# PSM_components.net
KiCad netlist of a schematic drawn in Altium Designer
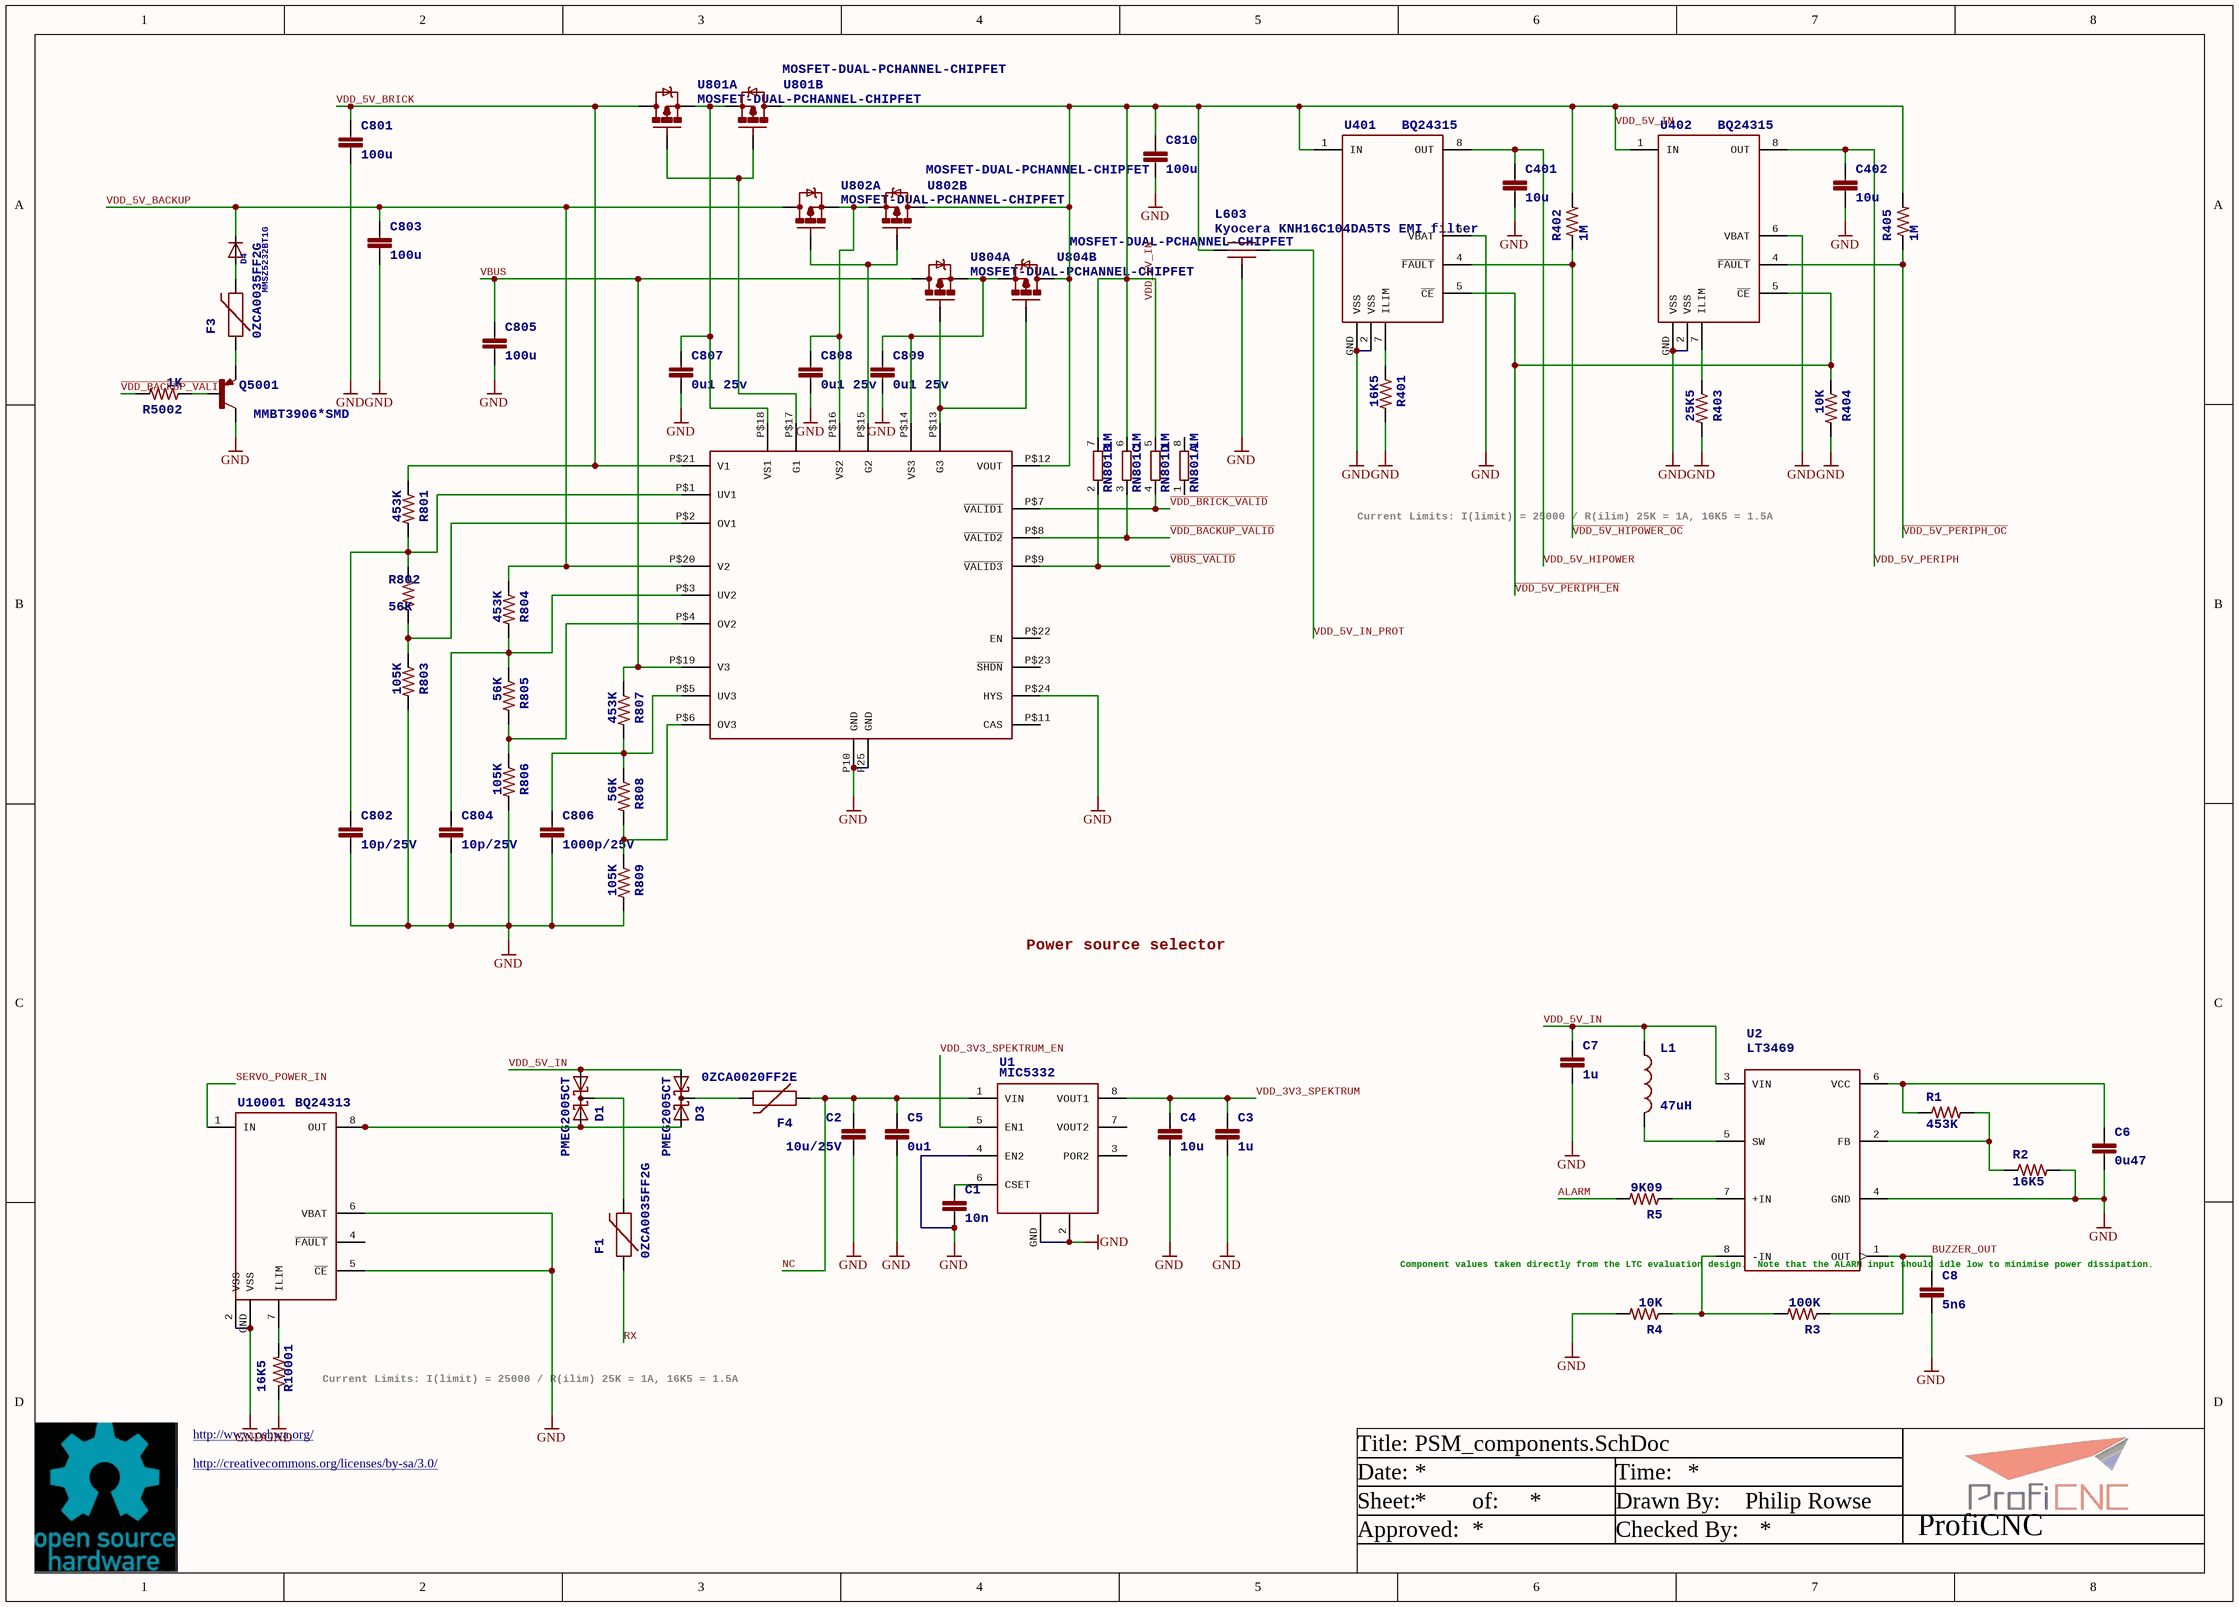
[diagram p0: PSM_components.SchDoc]

(export (version "E")
  (design (tool "Eeschema 10.0.6"))
  (components
    (comp (ref "C1") (value "10n") (footprint "PSM:0402-CAP") (libsource (lib "PSM_REV_C") (part "CAP0402")))
    (comp (ref "C2")
      (value "10u/25V")
      (footprint "PSM:0805-CAP")
      (libsource (lib "PSM_REV_C") (part "CAP0805"))
    )
    (comp (ref "C3") (value "1u") (footprint "PSM:0603-CAP") (libsource (lib "PSM_REV_C") (part "CAP0603")))
    (comp (ref "C4") (value "10u") (footprint "PSM:0603-CAP") (libsource (lib "PSM_REV_C") (part "CAP0603")))
    (comp (ref "C5") (value "0u1") (footprint "PSM:0402-CAP") (libsource (lib "PSM_REV_C") (part "CAP0402")))
    (comp (ref "C6") (value "0u47") (footprint "PSM:0402-CAP") (libsource (lib "PSM_REV_C") (part "CAP0402")))
    (comp (ref "C7") (value "1u") (footprint "PSM:0603-CAP") (libsource (lib "PSM_REV_C") (part "CAP0603")))
    (comp (ref "C8") (value "5n6") (footprint "PSM:0402-CAP") (libsource (lib "PSM_REV_C") (part "CAP0402")))
    (comp (ref "C401")
      (value "10u")
      (footprint "PSM:0603-CAP")
      (libsource (lib "PSM_REV_C") (part "CAP0603"))
    )
    (comp (ref "C402")
      (value "10u")
      (footprint "PSM:0603-CAP")
      (libsource (lib "PSM_REV_C") (part "CAP0603"))
    )
    (comp (ref "C801")
      (value "100u")
      (footprint "PSM:1206-CAP")
      (libsource (lib "PSM_REV_C") (part "CAP1206"))
    )
    (comp (ref "C802")
      (value "10p/25V")
      (footprint "PSM:0402-CAP")
      (libsource (lib "PSM_REV_C") (part "CAP0402"))
    )
    (comp (ref "C803")
      (value "100u")
      (footprint "PSM:1206-CAP")
      (libsource (lib "PSM_REV_C") (part "CAP1206"))
    )
    (comp (ref "C804")
      (value "10p/25V")
      (footprint "PSM:0402-CAP")
      (libsource (lib "PSM_REV_C") (part "CAP0402"))
    )
    (comp (ref "C805")
      (value "100u")
      (footprint "PSM:1206-CAP")
      (libsource (lib "PSM_REV_C") (part "CAP1206"))
    )
    (comp (ref "C806")
      (value "1000p/25V")
      (footprint "PSM:0402-CAP")
      (libsource (lib "PSM_REV_C") (part "CAP0402"))
    )
    (comp (ref "C807")
      (value "0u1 25v")
      (footprint "PSM:0402-CAP")
      (libsource (lib "PSM_REV_C") (part "CAP0402"))
    )
    (comp (ref "C808")
      (value "0u1 25v")
      (footprint "PSM:0402-CAP")
      (libsource (lib "PSM_REV_C") (part "CAP0402"))
    )
    (comp (ref "C809")
      (value "0u1 25v")
      (footprint "PSM:0402-CAP")
      (libsource (lib "PSM_REV_C") (part "CAP0402"))
    )
    (comp (ref "C810")
      (value "100u")
      (footprint "PSM:1206-CAP")
      (libsource (lib "PSM_REV_C") (part "CAP1206"))
    )
    (comp (ref "D1")
      (value "PMEG2005CT")
      (footprint "PSM:SOT23-3")
      (libsource (lib "PSM_REV_C") (part "PMEG2005CT"))
    )
    (comp (ref "D3")
      (value "PMEG2005CT")
      (footprint "PSM:SOT23-3")
      (libsource (lib "PSM_REV_C") (part "PMEG2005CT"))
    )
    (comp (ref "D4")
      (value "MMSZ5232BT1G")
      (footprint "PSM:SOD-123")
      (libsource (lib "PSM_REV_C") (part "DIODESOD-123"))
    )
    (comp (ref "F1")
      (value "0ZCA0035FF2G")
      (footprint "PSM:PTC-1206")
      (libsource (lib "PSM_REV_C") (part "PTCSMD"))
    )
    (comp (ref "F3")
      (value "0ZCA0035FF2G")
      (footprint "PSM:PTC-1206")
      (libsource (lib "PSM") (part "PTCSMD"))
    )
    (comp (ref "F4")
      (value "0ZCA0020FF2E")
      (footprint "PSM:PTC-1206")
      (libsource (lib "PSM_REV_C") (part "PTCSMD"))
    )
    (comp (ref "L1")
      (value "47uH")
      (footprint "PSM:0805-IND")
      (libsource (lib "PSM_REV_C") (part "INDUCTOR0805"))
    )
    (comp (ref "L603")
      (value "Kyocera KNH16C104DA5TS EMI filter")
      (footprint "PSM:KYOCERA-KNH16-DA")
      (libsource (lib "PSM_REV_C") (part "KNH16C104DA5TS"))
    )
    (comp (ref "Q5001")
      (value "MMBT3906*SMD")
      (footprint "PSM:SOT23-BEC")
      (libsource (lib "PSM_REV_C") (part "MMBT3906*SMD"))
    )
    (comp (ref "R1")
      (value "453K")
      (footprint "PSM:0402-RES")
      (libsource (lib "PSM_REV_C") (part "RESISTOR0402-RES"))
    )
    (comp (ref "R2")
      (value "16K5")
      (footprint "PSM:0402-RES")
      (libsource (lib "PSM_REV_C") (part "RESISTOR0402-RES"))
    )
    (comp (ref "R3")
      (value "100K")
      (footprint "PSM:0402-RES")
      (libsource (lib "PSM_REV_C") (part "RESISTOR0402-RES"))
    )
    (comp (ref "R4")
      (value "10K")
      (footprint "PSM:0402-RES")
      (libsource (lib "PSM_REV_C") (part "RESISTOR0402-RES"))
    )
    (comp (ref "R5")
      (value "9K09")
      (footprint "PSM:0402-RES")
      (libsource (lib "PSM_REV_C") (part "RESISTOR0402-RES"))
    )
    (comp (ref "R401")
      (value "16K5")
      (footprint "PSM:0402-RES")
      (libsource (lib "altium-import") (part "root_3_RESISTOR0402-RES_"))
    )
    (comp (ref "R402")
      (value "1M")
      (footprint "PSM:0402-RES")
      (libsource (lib "PSM_REV_C") (part "RESISTOR0402-RES"))
    )
    (comp (ref "R403")
      (value "25K5")
      (footprint "PSM:0402-RES")
      (libsource (lib "PSM_REV_C") (part "RESISTOR0402-RES"))
    )
    (comp (ref "R404")
      (value "10K")
      (footprint "PSM:0402-RES")
      (libsource (lib "PSM_REV_C") (part "RESISTOR0402-RES"))
    )
    (comp (ref "R405")
      (value "1M")
      (footprint "PSM:0402-RES")
      (libsource (lib "PSM_REV_C") (part "RESISTOR0402-RES"))
    )
    (comp (ref "R801")
      (value "453K")
      (footprint "PSM:0402-RES")
      (libsource (lib "PSM_REV_C") (part "RESISTOR0402-RES"))
    )
    (comp (ref "R802")
      (value "56K")
      (footprint "PSM:0402-RES")
      (libsource (lib "PSM_REV_C") (part "RESISTOR0402-RES_1"))
    )
    (comp (ref "R803")
      (value "105K")
      (footprint "PSM:0402-RES")
      (libsource (lib "PSM_REV_C") (part "RESISTOR0402-RES"))
    )
    (comp (ref "R804")
      (value "453K")
      (footprint "PSM:0402-RES")
      (libsource (lib "PSM_REV_C") (part "RESISTOR0402-RES"))
    )
    (comp (ref "R805")
      (value "56K")
      (footprint "PSM:0402-RES")
      (libsource (lib "PSM_REV_C") (part "RESISTOR0402-RES"))
    )
    (comp (ref "R806")
      (value "105K")
      (footprint "PSM:0402-RES")
      (libsource (lib "PSM_REV_C") (part "RESISTOR0402-RES"))
    )
    (comp (ref "R807")
      (value "453K")
      (footprint "PSM:0402-RES")
      (libsource (lib "PSM_REV_C") (part "RESISTOR0402-RES"))
    )
    (comp (ref "R808")
      (value "56K")
      (footprint "PSM:0402-RES")
      (libsource (lib "PSM_REV_C") (part "RESISTOR0402-RES"))
    )
    (comp (ref "R809")
      (value "105K")
      (footprint "PSM:0402-RES")
      (libsource (lib "PSM_REV_C") (part "RESISTOR0402-RES"))
    )
    (comp (ref "R5002")
      (value "1K")
      (footprint "PSM:0402-RES")
      (libsource (lib "PSM_REV_C") (part "RESISTOR0402-RES"))
    )
    (comp (ref "R10001")
      (value "16K5")
      (footprint "PSM:0402-RES")
      (libsource (lib "PSM_REV_C") (part "RESISTOR0402-RES"))
    )
    (comp (ref "RN801")
      (value "1M")
      (footprint "EXB28V")
      (description "RES ARRAY 1M OHM 4 RES 0804")
      (libsource (lib "PSM_REV_C") (part "4R-NEXB28V"))
    )
    (comp (ref "U1")
      (value "MIC5332")
      (footprint "PSM:MLF-8-EPAD")
      (libsource (lib "PSM_REV_C") (part "MIC5332"))
    )
    (comp (ref "U2") (value "LT3469") (footprint "PSM:SOT23-8") (libsource (lib "PSM_REV_C") (part "LT3469")))
    (comp (ref "U401")
      (value "BQ24315")
      (footprint "QFN8-DSG")
      (libsource (lib "PSM_REV_C") (part "BQ24315"))
    )
    (comp (ref "U402")
      (value "BQ24315")
      (footprint "QFN8-DSG")
      (libsource (lib "PSM_REV_C") (part "BQ24315"))
    )
    (comp (ref "U801")
      (value "MOSFET-DUAL-PCHANNEL-CHIPFET")
      (footprint "PSM:1206-8")
      (description "MOSFET 2P-CH 20V 2.9A CHIPFET")
      (libsource (lib "") (part "MOSFET-DUAL-PCHANNEL-CHIPFET_1"))
    )
    (comp (ref "U802")
      (value "MOSFET-DUAL-PCHANNEL-CHIPFET")
      (footprint "PSM:1206-8")
      (description "MOSFET 2P-CH 20V 2.9A CHIPFET")
      (libsource (lib "") (part "MOSFET-DUAL-PCHANNEL-CHIPFET_1"))
    )
    (comp (ref "U803")
      (value "LTC4417")
      (footprint "PSM:MO-220")
      (libsource (lib "altium-import") (part "root_0_LTC4117_"))
    )
    (comp (ref "U804")
      (value "MOSFET-DUAL-PCHANNEL-CHIPFET")
      (footprint "PSM:1206-8")
      (description "MOSFET 2P-CH 20V 2.9A CHIPFET")
      (libsource (lib "PSM_REV_C") (part "MOSFET-DUAL-PCHANNEL-CHIPFET"))
    )
    (comp (ref "U10001")
      (value "BQ24313")
      (footprint "QFN8-DSG")
      (libsource (lib "PSM_REV_C") (part "BQ24313"))
    )
  )
  (nets
    (net (code "1") (name "/ALARM") (class "Default")
      (node (ref "R5") (pin "P$2") (pinfunction "2_P$2") (pintype "passive"))
    )
    (net (code "2") (name "/BUZZER_OUT") (class "Default")
      (node (ref "C8") (pin "P$1") (pinfunction "1_P$1") (pintype "passive"))
      (node (ref "R3") (pin "P$1") (pinfunction "1_P$1") (pintype "passive"))
      (node (ref "U2") (pin "1") (pinfunction "OUT_1") (pintype "output"))
    )
    (net (code "3") (name "/NC") (class "Default")
      (node (ref "C2") (pin "P$1") (pinfunction "1_P$1") (pintype "passive"))
      (node (ref "C5") (pin "P$1") (pinfunction "1_P$1") (pintype "passive"))
      (node (ref "F4") (pin "1") (pinfunction "1_1") (pintype "passive"))
      (node (ref "U1") (pin "1") (pinfunction "VIN_1") (pintype "passive"))
    )
    (net (code "4") (name "/RX") (class "Default")
      (node (ref "F1") (pin "1") (pinfunction "1_1") (pintype "passive"))
    )
    (net (code "5") (name "/SERVO_POWER_IN") (class "Default")
      (node (ref "U10001") (pin "1") (pinfunction "IN_1") (pintype "passive"))
    )
    (net (code "6") (name "/VBUS") (class "Default")
      (node (ref "C805") (pin "P$1") (pinfunction "1_P$1") (pintype "passive"))
      (node (ref "R807") (pin "P$1") (pinfunction "1_P$1") (pintype "passive"))
      (node (ref "U803") (pin "P$19") (pinfunction "V3_P$19") (pintype "passive"))
      (node (ref "U804") (pin "P7") (pinfunction "D_P7") (pintype "passive"))
    )
    (net (code "7") (name "/VDD_3V3_SPEKTRUM") (class "Default")
      (node (ref "C3") (pin "P$1") (pinfunction "1_P$1") (pintype "passive"))
      (node (ref "C4") (pin "P$1") (pinfunction "1_P$1") (pintype "passive"))
      (node (ref "U1") (pin "8") (pinfunction "VOUT1_8") (pintype "passive"))
    )
    (net (code "8") (name "/VDD_3V3_SPEKTRUM_EN") (class "Default")
      (node (ref "U1") (pin "5") (pinfunction "EN1_5") (pintype "passive"))
    )
    (net (code "9") (name "/VDD_5V_BACKUP") (class "Default")
      (node (ref "C803") (pin "P$1") (pinfunction "1_P$1") (pintype "passive"))
      (node (ref "D4") (pin "C") (pinfunction "C_C") (pintype "passive"))
      (node (ref "R804") (pin "P$1") (pinfunction "1_P$1") (pintype "passive"))
      (node (ref "U802") (pin "P7") (pinfunction "D_P7") (pintype "passive"))
      (node (ref "U803") (pin "P$20") (pinfunction "V2_P$20") (pintype "passive"))
    )
    (net (code "10") (name "/VDD_5V_BRICK") (class "Default")
      (node (ref "C801") (pin "P$1") (pinfunction "1_P$1") (pintype "passive"))
      (node (ref "R801") (pin "P$1") (pinfunction "1_P$1") (pintype "passive"))
      (node (ref "U801") (pin "P7") (pinfunction "D_P7") (pintype "passive"))
      (node (ref "U803") (pin "P$21") (pinfunction "V1_P$21") (pintype "passive"))
    )
    (net (code "11") (name "/VDD_5V_HIPOWER") (class "Default")
      (node (ref "C401") (pin "P$1") (pinfunction "1_P$1") (pintype "passive"))
      (node (ref "U401") (pin "8") (pinfunction "OUT_8") (pintype "passive"))
    )
    (net (code "12") (name "/VDD_5V_IN") (class "Default")
      (node (ref "C7") (pin "P$1") (pinfunction "1_P$1") (pintype "passive"))
      (node (ref "C810") (pin "P$1") (pinfunction "1_P$1") (pintype "passive"))
      (node (ref "D1") (pin "1") (pinfunction "A1_1") (pintype "passive"))
      (node (ref "D3") (pin "1") (pinfunction "A1_1") (pintype "passive"))
      (node (ref "L1") (pin "P$1") (pinfunction "1_P$1") (pintype "passive"))
      (node (ref "L603") (pin "P$1") (pinfunction "P$1_P$1") (pintype "passive"))
      (node (ref "R402") (pin "P$2") (pinfunction "2_P$2") (pintype "passive"))
      (node (ref "R405") (pin "P$2") (pinfunction "2_P$2") (pintype "passive"))
      (node (ref "RN801") (pin "5") (pinfunction "2_5") (pintype "passive"))
      (node (ref "RN801") (pin "6") (pinfunction "2_6") (pintype "passive"))
      (node (ref "RN801") (pin "7") (pinfunction "2_7") (pintype "passive"))
      (node (ref "U2") (pin "3") (pinfunction "VIN_3") (pintype "power_in"))
      (node (ref "U401") (pin "1") (pinfunction "IN_1") (pintype "passive"))
      (node (ref "U402") (pin "1") (pinfunction "IN_1") (pintype "passive"))
      (node (ref "U801") (pin "P5") (pinfunction "D_P5") (pintype "passive"))
      (node (ref "U802") (pin "P5") (pinfunction "D_P5") (pintype "passive"))
      (node (ref "U803") (pin "P$12") (pinfunction "VOUT_P$12") (pintype "passive"))
      (node (ref "U804") (pin "P5") (pinfunction "D_P5") (pintype "passive"))
    )
    (net (code "13") (name "/VDD_5V_IN_PROT") (class "Default")
      (node (ref "L603") (pin "P$2") (pinfunction "P$2_P$2") (pintype "passive"))
    )
    (net (code "14") (name "/VDD_5V_PERIPH") (class "Default")
      (node (ref "C402") (pin "P$1") (pinfunction "1_P$1") (pintype "passive"))
      (node (ref "U402") (pin "8") (pinfunction "OUT_8") (pintype "passive"))
    )
    (net (code "15") (name "/~{VBUS_VALID}") (class "Default")
      (node (ref "RN801") (pin "2") (pinfunction "1_2") (pintype "passive"))
      (node (ref "U803") (pin "P$9") (pinfunction "~{VALID3}_P$9") (pintype "passive"))
    )
    (net (code "16") (name "/~{VDD_5V_HIPOWER_OC}") (class "Default")
      (node (ref "R402") (pin "P$1") (pinfunction "1_P$1") (pintype "passive"))
      (node (ref "U401") (pin "4") (pinfunction "~{FAULT}_4") (pintype "passive"))
    )
    (net (code "17") (name "/~{VDD_5V_PERIPH_EN}") (class "Default")
      (node (ref "R404") (pin "P$1") (pinfunction "1_P$1") (pintype "passive"))
      (node (ref "U401") (pin "5") (pinfunction "~{CE}_5") (pintype "passive"))
      (node (ref "U402") (pin "5") (pinfunction "~{CE}_5") (pintype "passive"))
    )
    (net (code "18") (name "/~{VDD_5V_PERIPH_OC}") (class "Default")
      (node (ref "R405") (pin "P$1") (pinfunction "1_P$1") (pintype "passive"))
      (node (ref "U402") (pin "4") (pinfunction "~{FAULT}_4") (pintype "passive"))
    )
    (net (code "19") (name "/~{VDD_BACKUP_VALID}") (class "Default")
      (node (ref "R5002") (pin "P$2") (pinfunction "2_P$2") (pintype "passive"))
      (node (ref "RN801") (pin "3") (pinfunction "1_3") (pintype "passive"))
      (node (ref "U803") (pin "P$8") (pinfunction "~{VALID2}_P$8") (pintype "passive"))
    )
    (net (code "20") (name "/~{VDD_BRICK_VALID}") (class "Default")
      (node (ref "RN801") (pin "4") (pinfunction "1_4") (pintype "passive"))
      (node (ref "U803") (pin "P$7") (pinfunction "~{VALID1}_P$7") (pintype "passive"))
    )
    (net (code "21") (name "GND") (class "Default")
      (node (ref "C1") (pin "P$2") (pinfunction "2_P$2") (pintype "passive"))
      (node (ref "C2") (pin "P$2") (pinfunction "2_P$2") (pintype "passive"))
      (node (ref "C3") (pin "P$2") (pinfunction "2_P$2") (pintype "passive"))
      (node (ref "C4") (pin "P$2") (pinfunction "2_P$2") (pintype "passive"))
      (node (ref "C401") (pin "P$2") (pinfunction "2_P$2") (pintype "passive"))
      (node (ref "C402") (pin "P$2") (pinfunction "2_P$2") (pintype "passive"))
      (node (ref "C5") (pin "P$2") (pinfunction "2_P$2") (pintype "passive"))
      (node (ref "C6") (pin "P$2") (pinfunction "2_P$2") (pintype "passive"))
      (node (ref "C7") (pin "P$2") (pinfunction "2_P$2") (pintype "passive"))
      (node (ref "C8") (pin "P$2") (pinfunction "2_P$2") (pintype "passive"))
      (node (ref "C801") (pin "P$2") (pinfunction "2_P$2") (pintype "passive"))
      (node (ref "C802") (pin "P$2") (pinfunction "2_P$2") (pintype "passive"))
      (node (ref "C803") (pin "P$2") (pinfunction "2_P$2") (pintype "passive"))
      (node (ref "C804") (pin "P$2") (pinfunction "2_P$2") (pintype "passive"))
      (node (ref "C805") (pin "P$2") (pinfunction "2_P$2") (pintype "passive"))
      (node (ref "C806") (pin "P$2") (pinfunction "2_P$2") (pintype "passive"))
      (node (ref "C807") (pin "P$2") (pinfunction "2_P$2") (pintype "passive"))
      (node (ref "C808") (pin "P$2") (pinfunction "2_P$2") (pintype "passive"))
      (node (ref "C809") (pin "P$2") (pinfunction "2_P$2") (pintype "passive"))
      (node (ref "C810") (pin "P$2") (pinfunction "2_P$2") (pintype "passive"))
      (node (ref "L603") (pin "GND") (pinfunction "GND_GND") (pintype "passive"))
      (node (ref "Q5001") (pin "C") (pinfunction "C_C") (pintype "passive"))
      (node (ref "R10001") (pin "P$1") (pinfunction "1_P$1") (pintype "passive"))
      (node (ref "R2") (pin "P$2") (pinfunction "2_P$2") (pintype "passive"))
      (node (ref "R4") (pin "P$2") (pinfunction "2_P$2") (pintype "passive"))
      (node (ref "R401") (pin "P$2") (pinfunction "2_P$2") (pintype "passive"))
      (node (ref "R403") (pin "P$2") (pinfunction "2_P$2") (pintype "passive"))
      (node (ref "R404") (pin "P$2") (pinfunction "2_P$2") (pintype "passive"))
      (node (ref "R803") (pin "P$2") (pinfunction "2_P$2") (pintype "passive"))
      (node (ref "R806") (pin "P$2") (pinfunction "2_P$2") (pintype "passive"))
      (node (ref "R809") (pin "P$2") (pinfunction "2_P$2") (pintype "passive"))
      (node (ref "U1") (pin "2") (pinfunction "GND_2") (pintype "power_in"))
      (node (ref "U1") (pin "4") (pinfunction "EN2_4") (pintype "passive"))
      (node (ref "U1") (pin "GND") (pinfunction "GND_GND") (pintype "power_in"))
      (node (ref "U10001") (pin "2") (pinfunction "VSS_2") (pintype "passive"))
      (node (ref "U10001") (pin "5") (pinfunction "~{CE}_5") (pintype "passive"))
      (node (ref "U10001") (pin "6") (pinfunction "VBAT_6") (pintype "passive"))
      (node (ref "U10001") (pin "GND") (pinfunction "VSS_GND") (pintype "passive"))
      (node (ref "U2") (pin "4") (pinfunction "GND_4") (pintype "power_in"))
      (node (ref "U401") (pin "2") (pinfunction "VSS_2") (pintype "passive"))
      (node (ref "U401") (pin "6") (pinfunction "VBAT_6") (pintype "passive"))
      (node (ref "U401") (pin "GND") (pinfunction "VSS_GND") (pintype "passive"))
      (node (ref "U402") (pin "2") (pinfunction "VSS_2") (pintype "passive"))
      (node (ref "U402") (pin "6") (pinfunction "VBAT_6") (pintype "passive"))
      (node (ref "U402") (pin "GND") (pinfunction "VSS_GND") (pintype "passive"))
      (node (ref "U803") (pin "P$24") (pinfunction "HYS_P$24") (pintype "passive"))
      (node (ref "U803") (pin "P10") (pinfunction "GND_P10") (pintype "passive"))
      (node (ref "U803") (pin "P25") (pinfunction "GND_P25") (pintype "passive"))
    )
    (net (code "22") (name "Net-(C1-1)") (class "Default")
      (node (ref "C1") (pin "P$1") (pinfunction "1_P$1") (pintype "passive"))
      (node (ref "U1") (pin "6") (pinfunction "CSET_6") (pintype "passive"))
    )
    (net (code "23") (name "Net-(C6-1)") (class "Default")
      (node (ref "C6") (pin "P$1") (pinfunction "1_P$1") (pintype "passive"))
      (node (ref "R1") (pin "P$1") (pinfunction "1_P$1") (pintype "passive"))
      (node (ref "U2") (pin "6") (pinfunction "VCC_6") (pintype "passive"))
    )
    (net (code "24") (name "Net-(C802-1)") (class "Default")
      (node (ref "C802") (pin "P$1") (pinfunction "1_P$1") (pintype "passive"))
      (node (ref "R801") (pin "P$2") (pinfunction "2_P$2") (pintype "passive"))
      (node (ref "R802") (pin "P$1") (pinfunction "1_P$1") (pintype "passive"))
      (node (ref "U803") (pin "P$1") (pinfunction "UV1_P$1") (pintype "passive"))
    )
    (net (code "25") (name "Net-(C804-1)") (class "Default")
      (node (ref "C804") (pin "P$1") (pinfunction "1_P$1") (pintype "passive"))
      (node (ref "R804") (pin "P$2") (pinfunction "2_P$2") (pintype "passive"))
      (node (ref "R805") (pin "P$1") (pinfunction "1_P$1") (pintype "passive"))
      (node (ref "U803") (pin "P$3") (pinfunction "UV2_P$3") (pintype "passive"))
    )
    (net (code "26") (name "Net-(C806-1)") (class "Default")
      (node (ref "C806") (pin "P$1") (pinfunction "1_P$1") (pintype "passive"))
      (node (ref "R807") (pin "P$2") (pinfunction "2_P$2") (pintype "passive"))
      (node (ref "R808") (pin "P$1") (pinfunction "1_P$1") (pintype "passive"))
      (node (ref "U803") (pin "P$5") (pinfunction "UV3_P$5") (pintype "passive"))
    )
    (net (code "27") (name "Net-(C807-1)") (class "Default")
      (node (ref "C807") (pin "P$1") (pinfunction "1_P$1") (pintype "passive"))
      (node (ref "U801") (pin "P1") (pinfunction "S_P1") (pintype "passive"))
      (node (ref "U801") (pin "P3") (pinfunction "S_P3") (pintype "passive"))
      (node (ref "U803") (pin "P$18") (pinfunction "VS1_P$18") (pintype "passive"))
    )
    (net (code "28") (name "Net-(C808-1)") (class "Default")
      (node (ref "C808") (pin "P$1") (pinfunction "1_P$1") (pintype "passive"))
      (node (ref "U802") (pin "P1") (pinfunction "S_P1") (pintype "passive"))
      (node (ref "U802") (pin "P3") (pinfunction "S_P3") (pintype "passive"))
      (node (ref "U803") (pin "P$16") (pinfunction "VS2_P$16") (pintype "passive"))
    )
    (net (code "29") (name "Net-(C809-1)") (class "Default")
      (node (ref "C809") (pin "P$1") (pinfunction "1_P$1") (pintype "passive"))
      (node (ref "U803") (pin "P$14") (pinfunction "VS3_P$14") (pintype "passive"))
      (node (ref "U804") (pin "P1") (pinfunction "S_P1") (pintype "passive"))
      (node (ref "U804") (pin "P3") (pinfunction "S_P3") (pintype "passive"))
    )
    (net (code "30") (name "Net-(D1-A2)") (class "Default")
      (node (ref "D1") (pin "2") (pinfunction "A2_2") (pintype "passive"))
      (node (ref "D3") (pin "2") (pinfunction "A2_2") (pintype "passive"))
      (node (ref "U10001") (pin "8") (pinfunction "OUT_8") (pintype "passive"))
    )
    (net (code "31") (name "Net-(D1-CC)") (class "Default")
      (node (ref "D1") (pin "3") (pinfunction "CC_3") (pintype "passive"))
      (node (ref "F1") (pin "2") (pinfunction "2_2") (pintype "passive"))
    )
    (net (code "32") (name "Net-(D3-CC)") (class "Default")
      (node (ref "D3") (pin "3") (pinfunction "CC_3") (pintype "passive"))
      (node (ref "F4") (pin "2") (pinfunction "2_2") (pintype "passive"))
    )
    (net (code "33") (name "Net-(D4-PadA)") (class "Default")
      (node (ref "D4") (pin "A") (pinfunction "A_A") (pintype "passive"))
      (node (ref "F3") (pin "2") (pinfunction "2_2") (pintype "passive"))
    )
    (net (code "34") (name "Net-(F3-Pad1)") (class "Default")
      (node (ref "F3") (pin "1") (pinfunction "1_1") (pintype "passive"))
      (node (ref "Q5001") (pin "E") (pinfunction "E_E") (pintype "passive"))
    )
    (net (code "35") (name "Net-(L1-2)") (class "Default")
      (node (ref "L1") (pin "P$2") (pinfunction "2_P$2") (pintype "passive"))
      (node (ref "U2") (pin "5") (pinfunction "SW_5") (pintype "passive"))
    )
    (net (code "36") (name "Net-(R1-2)") (class "Default")
      (node (ref "R1") (pin "P$2") (pinfunction "2_P$2") (pintype "passive"))
      (node (ref "R2") (pin "P$1") (pinfunction "1_P$1") (pintype "passive"))
      (node (ref "U2") (pin "2") (pinfunction "FB_2") (pintype "passive"))
    )
    (net (code "37") (name "Net-(R3-2)") (class "Default")
      (node (ref "R3") (pin "P$2") (pinfunction "2_P$2") (pintype "passive"))
      (node (ref "R4") (pin "P$1") (pinfunction "1_P$1") (pintype "passive"))
      (node (ref "U2") (pin "8") (pinfunction "-IN_8") (pintype "passive"))
    )
    (net (code "38") (name "Net-(R5-1)") (class "Default")
      (node (ref "R5") (pin "P$1") (pinfunction "1_P$1") (pintype "passive"))
      (node (ref "U2") (pin "7") (pinfunction "+IN_7") (pintype "passive"))
    )
    (net (code "39") (name "Net-(R401-1)") (class "Default")
      (node (ref "R401") (pin "P$1") (pinfunction "1_P$1") (pintype "passive"))
      (node (ref "U401") (pin "7") (pinfunction "ILIM_7") (pintype "passive"))
    )
    (net (code "40") (name "Net-(R403-1)") (class "Default")
      (node (ref "R403") (pin "P$1") (pinfunction "1_P$1") (pintype "passive"))
      (node (ref "U402") (pin "7") (pinfunction "ILIM_7") (pintype "passive"))
    )
    (net (code "41") (name "Net-(R802-2)") (class "Default")
      (node (ref "R802") (pin "P$2") (pinfunction "2_P$2") (pintype "passive"))
      (node (ref "R803") (pin "P$1") (pinfunction "1_P$1") (pintype "passive"))
      (node (ref "U803") (pin "P$2") (pinfunction "OV1_P$2") (pintype "passive"))
    )
    (net (code "42") (name "Net-(R805-2)") (class "Default")
      (node (ref "R805") (pin "P$2") (pinfunction "2_P$2") (pintype "passive"))
      (node (ref "R806") (pin "P$1") (pinfunction "1_P$1") (pintype "passive"))
      (node (ref "U803") (pin "P$4") (pinfunction "OV2_P$4") (pintype "passive"))
    )
    (net (code "43") (name "Net-(R808-2)") (class "Default")
      (node (ref "R808") (pin "P$2") (pinfunction "2_P$2") (pintype "passive"))
      (node (ref "R809") (pin "P$1") (pinfunction "1_P$1") (pintype "passive"))
      (node (ref "U803") (pin "P$6") (pinfunction "OV3_P$6") (pintype "passive"))
    )
    (net (code "44") (name "Net-(R5002-1)") (class "Default")
      (node (ref "Q5001") (pin "B") (pinfunction "B_B") (pintype "passive"))
      (node (ref "R5002") (pin "P$1") (pinfunction "1_P$1") (pintype "passive"))
    )
    (net (code "45") (name "Net-(R10001-2)") (class "Default")
      (node (ref "R10001") (pin "P$2") (pinfunction "2_P$2") (pintype "passive"))
      (node (ref "U10001") (pin "7") (pinfunction "ILIM_7") (pintype "passive"))
    )
    (net (code "46") (name "Net-(U801A-G)") (class "Default")
      (node (ref "U801") (pin "P2") (pinfunction "G_P2") (pintype "passive"))
      (node (ref "U801") (pin "P4") (pinfunction "G_P4") (pintype "passive"))
      (node (ref "U803") (pin "P$17") (pinfunction "G1_P$17") (pintype "passive"))
    )
    (net (code "47") (name "Net-(U802A-G)") (class "Default")
      (node (ref "U802") (pin "P2") (pinfunction "G_P2") (pintype "passive"))
      (node (ref "U802") (pin "P4") (pinfunction "G_P4") (pintype "passive"))
      (node (ref "U803") (pin "P$15") (pinfunction "G2_P$15") (pintype "passive"))
    )
    (net (code "48") (name "Net-(U803-G3)") (class "Default")
      (node (ref "U803") (pin "P$13") (pinfunction "G3_P$13") (pintype "passive"))
      (node (ref "U804") (pin "P2") (pinfunction "G_P2") (pintype "passive"))
      (node (ref "U804") (pin "P4") (pinfunction "G_P4") (pintype "passive"))
    )
    (net (code "49") (name "unconnected-(RN801-Pad1)") (class "Default")
      (node (ref "RN801") (pin "1") (pinfunction "1_1") (pintype "passive"))
    )
    (net (code "50") (name "unconnected-(RN801A-2-Pad8)") (class "Default")
      (node (ref "RN801") (pin "8") (pinfunction "2_8") (pintype "passive"))
    )
    (net (code "51") (name "unconnected-(U1-POR2-Pad3)") (class "Default")
      (node (ref "U1") (pin "3") (pinfunction "POR2_3") (pintype "passive"))
    )
    (net (code "52") (name "unconnected-(U1-VOUT2-Pad7)") (class "Default")
      (node (ref "U1") (pin "7") (pinfunction "VOUT2_7") (pintype "passive"))
    )
    (net (code "53") (name "unconnected-(U803-CAS-PadP$11)") (class "Default")
      (node (ref "U803") (pin "P$11") (pinfunction "CAS_P$11") (pintype "passive"))
    )
    (net (code "54") (name "unconnected-(U803-EN-PadP$22)") (class "Default")
      (node (ref "U803") (pin "P$22") (pinfunction "EN_P$22") (pintype "passive"))
    )
    (net (code "55") (name "unconnected-(U803-~{SHDN}-PadP$23)") (class "Default")
      (node (ref "U803") (pin "P$23") (pinfunction "~{SHDN}_P$23") (pintype "passive"))
    )
    (net (code "56") (name "unconnected-(U10001-~{FAULT}-Pad4)") (class "Default")
      (node (ref "U10001") (pin "4") (pinfunction "~{FAULT}_4") (pintype "passive"))
    )
  )
)
